# DIGITAL_OUTPUT.net
KiCad netlist of a schematic drawn in Altium Designer
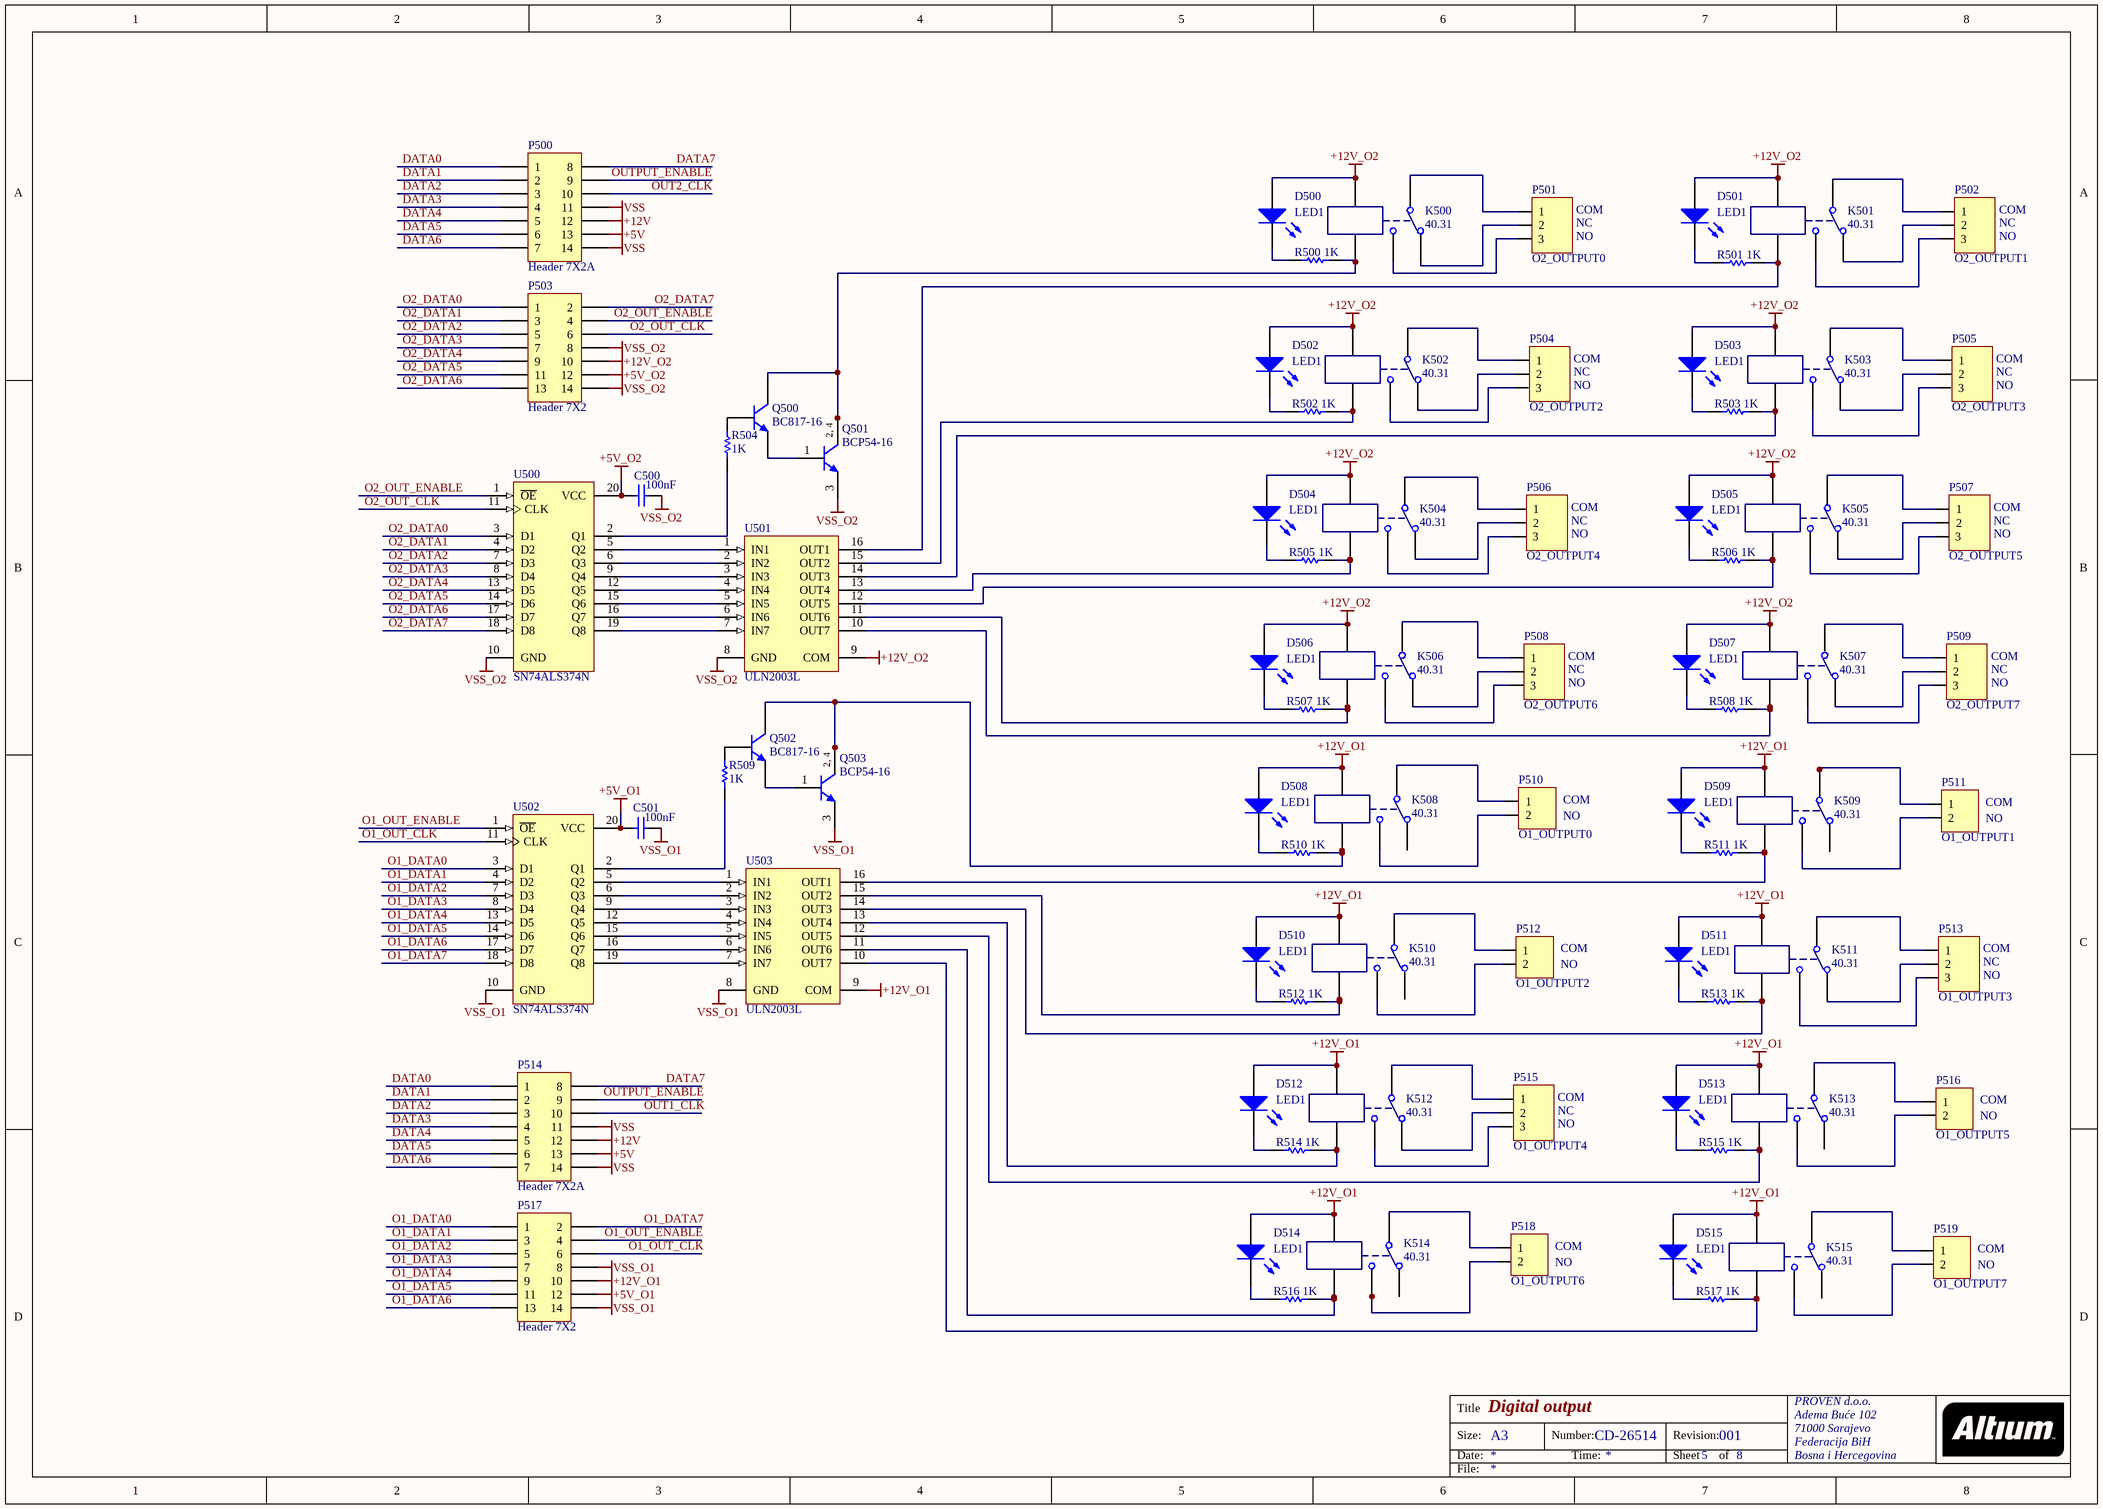
[diagram p0: DIGITAL_OUTPUT.SchDoc]

(export (version "E")
  (design (tool "Eeschema 10.0.6"))
  (components
    (comp (ref "C500")
      (value "100nF")
      (footprint "1206")
      (description "Ceramic Chip Capacitor - Standard")
      (fields (field (name "PUBLISHER") "Altium Limited"))
      (libsource (lib "KEMET Chip Capacitor") (part "C1206"))
    )
    (comp (ref "C501")
      (value "100nF")
      (footprint "1206")
      (description "Ceramic Chip Capacitor - Standard")
      (fields (field (name "PUBLISHER") "Altium Limited"))
      (libsource (lib "KEMET Chip Capacitor") (part "C1206"))
    )
    (comp (ref "D500")
      (value "LED1")
      (footprint "LED-1")
      (description "Typical RED GaAs LED")
      (fields (field (name "PUBLISHER") "Altium Limited"))
      (libsource (lib "Miscellaneous Devices") (part "LED1"))
    )
    (comp (ref "D501")
      (value "LED1")
      (footprint "LED-1")
      (description "Typical RED GaAs LED")
      (fields (field (name "PUBLISHER") "Altium Limited"))
      (libsource (lib "Miscellaneous Devices") (part "LED1"))
    )
    (comp (ref "D502")
      (value "LED1")
      (footprint "LED-1")
      (description "Typical RED GaAs LED")
      (fields (field (name "PUBLISHER") "Altium Limited"))
      (libsource (lib "Miscellaneous Devices") (part "LED1"))
    )
    (comp (ref "D503")
      (value "LED1")
      (footprint "LED-1")
      (description "Typical RED GaAs LED")
      (fields (field (name "PUBLISHER") "Altium Limited"))
      (libsource (lib "Miscellaneous Devices") (part "LED1"))
    )
    (comp (ref "D504")
      (value "LED1")
      (footprint "LED-1")
      (description "Typical RED GaAs LED")
      (fields (field (name "PUBLISHER") "Altium Limited"))
      (libsource (lib "Miscellaneous Devices") (part "LED1"))
    )
    (comp (ref "D505")
      (value "LED1")
      (footprint "LED-1")
      (description "Typical RED GaAs LED")
      (fields (field (name "PUBLISHER") "Altium Limited"))
      (libsource (lib "Miscellaneous Devices") (part "LED1"))
    )
    (comp (ref "D506")
      (value "LED1")
      (footprint "LED-1")
      (description "Typical RED GaAs LED")
      (fields (field (name "PUBLISHER") "Altium Limited"))
      (libsource (lib "Miscellaneous Devices") (part "LED1"))
    )
    (comp (ref "D507")
      (value "LED1")
      (footprint "LED-1")
      (description "Typical RED GaAs LED")
      (fields (field (name "PUBLISHER") "Altium Limited"))
      (libsource (lib "Miscellaneous Devices") (part "LED1"))
    )
    (comp (ref "D508")
      (value "LED1")
      (footprint "LED-1")
      (description "Typical RED GaAs LED")
      (fields (field (name "PUBLISHER") "Altium Limited"))
      (libsource (lib "Miscellaneous Devices") (part "LED1"))
    )
    (comp (ref "D509")
      (value "LED1")
      (footprint "LED-1")
      (description "Typical RED GaAs LED")
      (fields (field (name "PUBLISHER") "Altium Limited"))
      (libsource (lib "Miscellaneous Devices") (part "LED1"))
    )
    (comp (ref "D510")
      (value "LED1")
      (footprint "LED-1")
      (description "Typical RED GaAs LED")
      (fields (field (name "PUBLISHER") "Altium Limited"))
      (libsource (lib "Miscellaneous Devices") (part "LED1"))
    )
    (comp (ref "D511")
      (value "LED1")
      (footprint "LED-1")
      (description "Typical RED GaAs LED")
      (fields (field (name "PUBLISHER") "Altium Limited"))
      (libsource (lib "Miscellaneous Devices") (part "LED1"))
    )
    (comp (ref "D512")
      (value "LED1")
      (footprint "LED-1")
      (description "Typical RED GaAs LED")
      (fields (field (name "PUBLISHER") "Altium Limited"))
      (libsource (lib "Miscellaneous Devices") (part "LED1"))
    )
    (comp (ref "D513")
      (value "LED1")
      (footprint "LED-1")
      (description "Typical RED GaAs LED")
      (fields (field (name "PUBLISHER") "Altium Limited"))
      (libsource (lib "Miscellaneous Devices") (part "LED1"))
    )
    (comp (ref "D514")
      (value "LED1")
      (footprint "LED-1")
      (description "Typical RED GaAs LED")
      (fields (field (name "PUBLISHER") "Altium Limited"))
      (libsource (lib "Miscellaneous Devices") (part "LED1"))
    )
    (comp (ref "D515")
      (value "LED1")
      (footprint "LED-1")
      (description "Typical RED GaAs LED")
      (fields (field (name "PUBLISHER") "Altium Limited"))
      (libsource (lib "Miscellaneous Devices") (part "LED1"))
    )
    (comp (ref "K500")
      (value "40.31")
      (footprint "40.31 FINDER")
      (libsource (lib "") (part "FINDER 40.31_10"))
    )
    (comp (ref "K501")
      (value "40.31")
      (footprint "40.31 FINDER")
      (libsource (lib "") (part "FINDER 40.31_3"))
    )
    (comp (ref "K502")
      (value "40.31")
      (footprint "40.31 FINDER")
      (libsource (lib "") (part "FINDER 40.31_1"))
    )
    (comp (ref "K503")
      (value "40.31")
      (footprint "40.31 FINDER")
      (libsource (lib "") (part "FINDER 40.31_5"))
    )
    (comp (ref "K504")
      (value "40.31")
      (footprint "40.31 FINDER")
      (libsource (lib "") (part "FINDER 40.31_4"))
    )
    (comp (ref "K505")
      (value "40.31")
      (footprint "40.31 FINDER")
      (libsource (lib "") (part "FINDER 40.31_2"))
    )
    (comp (ref "K506")
      (value "40.31")
      (footprint "40.31 FINDER")
      (libsource (lib "") (part "FINDER 40.31_7"))
    )
    (comp (ref "K507")
      (value "40.31")
      (footprint "40.31 FINDER")
      (libsource (lib "") (part "FINDER 40.31_9"))
    )
    (comp (ref "K508")
      (value "40.31")
      (footprint "40.31 FINDER")
      (libsource (lib "FINDER 40.31") (part "FINDER 40.31"))
    )
    (comp (ref "K509")
      (value "40.31")
      (footprint "40.31 FINDER")
      (libsource (lib "") (part "FINDER 40.31_6"))
    )
    (comp (ref "K510")
      (value "40.31")
      (footprint "40.31 FINDER")
      (libsource (lib "FINDER 40.31") (part "FINDER 40.31"))
    )
    (comp (ref "K511")
      (value "40.31")
      (footprint "40.31 FINDER")
      (libsource (lib "") (part "FINDER 40.31_6"))
    )
    (comp (ref "K512")
      (value "40.31")
      (footprint "40.31 FINDER")
      (libsource (lib "FINDER 40.31") (part "FINDER 40.31"))
    )
    (comp (ref "K513")
      (value "40.31")
      (footprint "40.31 FINDER")
      (libsource (lib "") (part "FINDER 40.31_6"))
    )
    (comp (ref "K514")
      (value "40.31")
      (footprint "40.31 FINDER")
      (libsource (lib "") (part "FINDER 40.31_8"))
    )
    (comp (ref "K515")
      (value "40.31")
      (footprint "40.31 FINDER")
      (libsource (lib "") (part "FINDER 40.31_6"))
    )
    (comp (ref "P500")
      (value "Header 7X2A")
      (footprint "HDR2X7_CEN")
      (description "Header, 7-Pin, Dual row")
      (fields (field (name "PUBLISHER") "Altium Limited"))
      (libsource (lib "Miscellaneous Connectors") (part "Header 7X2A"))
    )
    (comp (ref "P501")
      (value "O2_OUTPUT0")
      (footprint "TERMINAL BLOK")
      (description "Terminal blok")
      (libsource (lib "") (part "Terminal blok 3 pina_1"))
    )
    (comp (ref "P502")
      (value "O2_OUTPUT1")
      (footprint "TERMINAL BLOK")
      (description "Terminal blok")
      (libsource (lib "") (part "Terminal blok 3 pina_3"))
    )
    (comp (ref "P503")
      (value "Header 7X2")
      (footprint "HDR2X7")
      (description "Header, 7-Pin, Dual row")
      (fields (field (name "PUBLISHER") "Altium Limited"))
      (libsource (lib "Miscellaneous Connectors") (part "Header 7X2"))
    )
    (comp (ref "P504")
      (value "O2_OUTPUT2")
      (footprint "TERMINAL BLOK")
      (description "Terminal blok")
      (libsource (lib "") (part "Terminal blok 3 pina_2"))
    )
    (comp (ref "P505")
      (value "O2_OUTPUT3")
      (footprint "TERMINAL BLOK")
      (description "Terminal blok")
      (libsource (lib "TERMINAL_CONNECOR_3") (part "Terminal blok 3 pina"))
    )
    (comp (ref "P506")
      (value "O2_OUTPUT4")
      (footprint "TERMINAL BLOK")
      (description "Terminal blok")
      (libsource (lib "") (part "Terminal blok 3 pina_2"))
    )
    (comp (ref "P507")
      (value "O2_OUTPUT5")
      (footprint "TERMINAL BLOK")
      (description "Terminal blok")
      (libsource (lib "TERMINAL_CONNECOR_3") (part "Terminal blok 3 pina"))
    )
    (comp (ref "P508")
      (value "O2_OUTPUT6")
      (footprint "TERMINAL BLOK")
      (description "Terminal blok")
      (libsource (lib "") (part "Terminal blok 3 pina_2"))
    )
    (comp (ref "P509")
      (value "O2_OUTPUT7")
      (footprint "TERMINAL BLOK")
      (description "Terminal blok")
      (libsource (lib "TERMINAL_CONNECOR_3") (part "Terminal blok 3 pina"))
    )
    (comp (ref "P510")
      (value "O1_OUTPUT0")
      (footprint "TERMINAL BLOK 2")
      (description "Terminal blok 2")
      (libsource (lib "") (part "Terminal blok 2 pina_1"))
    )
    (comp (ref "P511")
      (value "O1_OUTPUT1")
      (footprint "TERMINAL BLOK 2")
      (description "Terminal blok 2")
      (libsource (lib "") (part "Terminal blok 2 pina_3"))
    )
    (comp (ref "P512")
      (value "O1_OUTPUT2")
      (footprint "TERMINAL BLOK 2")
      (description "Terminal blok 2")
      (libsource (lib "") (part "Terminal blok 2 pina_1"))
    )
    (comp (ref "P513")
      (value "O1_OUTPUT3")
      (footprint "TERMINAL BLOK")
      (description "Terminal blok")
      (libsource (lib "TERMINAL_CONNECOR_3") (part "Terminal blok 3 pina"))
    )
    (comp (ref "P514")
      (value "Header 7X2A")
      (footprint "HDR2X7_CEN")
      (description "Header, 7-Pin, Dual row")
      (fields (field (name "PUBLISHER") "Altium Limited"))
      (libsource (lib "Miscellaneous Connectors") (part "Header 7X2A"))
    )
    (comp (ref "P515")
      (value "O1_OUTPUT4")
      (footprint "TERMINAL BLOK")
      (description "Terminal blok")
      (libsource (lib "") (part "Terminal blok 3 pina_2"))
    )
    (comp (ref "P516")
      (value "O1_OUTPUT5")
      (footprint "TERMINAL BLOK 2")
      (description "Terminal blok 2")
      (libsource (lib "") (part "Terminal blok 2 pina_3"))
    )
    (comp (ref "P517")
      (value "Header 7X2")
      (footprint "HDR2X7")
      (description "Header, 7-Pin, Dual row")
      (fields (field (name "PUBLISHER") "Altium Limited"))
      (libsource (lib "Miscellaneous Connectors") (part "Header 7X2"))
    )
    (comp (ref "P518")
      (value "O1_OUTPUT6")
      (footprint "TERMINAL BLOK 2")
      (description "Terminal blok 2")
      (libsource (lib "") (part "Terminal blok 2 pina_2"))
    )
    (comp (ref "P519")
      (value "O1_OUTPUT7")
      (footprint "TERMINAL BLOK 2")
      (description "Terminal blok 2")
      (libsource (lib "TERMINAL_CONNECOR_2") (part "Terminal blok 2 pina"))
    )
    (comp (ref "Q500")
      (value "BC817-16")
      (footprint "SOT23_N")
      (description "NPN General-purpose Transistor")
      (fields (field (name "PUBLISHER") "Altium Limited"))
      (libsource (lib "Philips Discrete BJT - Low Power") (part "BC817-16"))
    )
    (comp (ref "Q501")
      (value "BCP54-16")
      (footprint "SOT223_N")
      (description "NPN Medium Power Transistor")
      (fields (field (name "PUBLISHER") "Altium Limited"))
      (libsource (lib "Philips Discrete BJT - Medium Power") (part "BCP54-16"))
    )
    (comp (ref "Q502")
      (value "BC817-16")
      (footprint "SOT23_N")
      (description "NPN General-purpose Transistor")
      (fields (field (name "PUBLISHER") "Altium Limited"))
      (libsource (lib "Philips Discrete BJT - Low Power") (part "BC817-16"))
    )
    (comp (ref "Q503")
      (value "BCP54-16")
      (footprint "SOT223_N")
      (description "NPN Medium Power Transistor")
      (fields (field (name "PUBLISHER") "Altium Limited"))
      (libsource (lib "Philips Discrete BJT - Medium Power") (part "BCP54-16"))
    )
    (comp (ref "R500")
      (value "1K")
      (footprint "ERA-0805")
      (fields (field (name "PUBLISHER") "Altium Limited"))
      (libsource (lib "Panasonic Resistor") (part "ERAS"))
    )
    (comp (ref "R501")
      (value "1K")
      (footprint "ERA-0805")
      (fields (field (name "PUBLISHER") "Altium Limited"))
      (libsource (lib "Panasonic Resistor") (part "ERAS"))
    )
    (comp (ref "R502")
      (value "1K")
      (footprint "ERA-0805")
      (fields (field (name "PUBLISHER") "Altium Limited"))
      (libsource (lib "Panasonic Resistor") (part "ERAS"))
    )
    (comp (ref "R503")
      (value "1K")
      (footprint "ERA-0805")
      (fields (field (name "PUBLISHER") "Altium Limited"))
      (libsource (lib "Panasonic Resistor") (part "ERAS"))
    )
    (comp (ref "R504")
      (value "1K")
      (footprint "ERA-0805")
      (fields (field (name "PUBLISHER") "Altium Limited"))
      (libsource (lib "Panasonic Resistor") (part "ERAS"))
    )
    (comp (ref "R505")
      (value "1K")
      (footprint "ERA-0805")
      (fields (field (name "PUBLISHER") "Altium Limited"))
      (libsource (lib "Panasonic Resistor") (part "ERAS"))
    )
    (comp (ref "R506")
      (value "1K")
      (footprint "ERA-0805")
      (fields (field (name "PUBLISHER") "Altium Limited"))
      (libsource (lib "Panasonic Resistor") (part "ERAS"))
    )
    (comp (ref "R507")
      (value "1K")
      (footprint "ERA-0805")
      (fields (field (name "PUBLISHER") "Altium Limited"))
      (libsource (lib "Panasonic Resistor") (part "ERAS"))
    )
    (comp (ref "R508")
      (value "1K")
      (footprint "ERA-0805")
      (fields (field (name "PUBLISHER") "Altium Limited"))
      (libsource (lib "Panasonic Resistor") (part "ERAS"))
    )
    (comp (ref "R509")
      (value "1K")
      (footprint "ERA-0805")
      (fields (field (name "PUBLISHER") "Altium Limited"))
      (libsource (lib "Panasonic Resistor") (part "ERAS"))
    )
    (comp (ref "R510")
      (value "1K")
      (footprint "ERA-0805")
      (fields (field (name "PUBLISHER") "Altium Limited"))
      (libsource (lib "Panasonic Resistor") (part "ERAS"))
    )
    (comp (ref "R511")
      (value "1K")
      (footprint "ERA-0805")
      (fields (field (name "PUBLISHER") "Altium Limited"))
      (libsource (lib "Panasonic Resistor") (part "ERAS"))
    )
    (comp (ref "R512")
      (value "1K")
      (footprint "ERA-0805")
      (fields (field (name "PUBLISHER") "Altium Limited"))
      (libsource (lib "Panasonic Resistor") (part "ERAS"))
    )
    (comp (ref "R513")
      (value "1K")
      (footprint "ERA-0805")
      (fields (field (name "PUBLISHER") "Altium Limited"))
      (libsource (lib "Panasonic Resistor") (part "ERAS"))
    )
    (comp (ref "R514")
      (value "1K")
      (footprint "ERA-0805")
      (fields (field (name "PUBLISHER") "Altium Limited"))
      (libsource (lib "Panasonic Resistor") (part "ERAS"))
    )
    (comp (ref "R515")
      (value "1K")
      (footprint "ERA-0805")
      (fields (field (name "PUBLISHER") "Altium Limited"))
      (libsource (lib "Panasonic Resistor") (part "ERAS"))
    )
    (comp (ref "R516")
      (value "1K")
      (footprint "ERA-0805")
      (fields (field (name "PUBLISHER") "Altium Limited"))
      (libsource (lib "Panasonic Resistor") (part "ERAS"))
    )
    (comp (ref "R517")
      (value "1K")
      (footprint "ERA-0805")
      (fields (field (name "PUBLISHER") "Altium Limited"))
      (libsource (lib "Panasonic Resistor") (part "ERAS"))
    )
    (comp (ref "U500")
      (value "SN74ALS374N")
      (footprint "N020D")
      (description "Octal D-Type Edge-Triggered Flip-Flop with 3-State Outputs")
      (fields (field (name "PUBLISHER") "Altium Limited"))
      (libsource (lib "TI Logic Flip-Flop") (part "SN74ALS374N"))
    )
    (comp (ref "U501")
      (value "ULN2003L")
      (footprint "L16_N")
      (description "High-Voltage, High-Current Darlington Array")
      (fields (field (name "PUBLISHER") "Altium Limited"))
      (libsource (lib "Allegro Interface Darlington Driver") (part "ULN2003L"))
    )
    (comp (ref "U502")
      (value "SN74ALS374N")
      (footprint "N020D")
      (description "Octal D-Type Edge-Triggered Flip-Flop with 3-State Outputs")
      (fields (field (name "PUBLISHER") "Altium Limited"))
      (libsource (lib "TI Logic Flip-Flop") (part "SN74ALS374N"))
    )
    (comp (ref "U503")
      (value "ULN2003L")
      (footprint "L16_N")
      (description "High-Voltage, High-Current Darlington Array")
      (fields (field (name "PUBLISHER") "Altium Limited"))
      (libsource (lib "Allegro Interface Darlington Driver") (part "ULN2003L"))
    )
  )
  (nets
    (net (code "1") (name "+5V") (class "Default")
      (node (ref "P500") (pin "13") (pinfunction "13_13") (pintype "passive"))
      (node (ref "P514") (pin "13") (pinfunction "13_13") (pintype "passive"))
    )
    (net (code "2") (name "+5V_O1") (class "Default")
      (node (ref "C501") (pin "1") (pinfunction "1_1") (pintype "passive"))
      (node (ref "P517") (pin "12") (pinfunction "12_12") (pintype "passive"))
      (node (ref "U502") (pin "20") (pinfunction "VCC_20") (pintype "power_in"))
    )
    (net (code "3") (name "+5V_O2") (class "Default")
      (node (ref "C500") (pin "1") (pinfunction "1_1") (pintype "passive"))
      (node (ref "P503") (pin "12") (pinfunction "12_12") (pintype "passive"))
      (node (ref "U500") (pin "20") (pinfunction "VCC_20") (pintype "power_in"))
    )
    (net (code "4") (name "+12V") (class "Default")
      (node (ref "P500") (pin "12") (pinfunction "12_12") (pintype "passive"))
      (node (ref "P514") (pin "12") (pinfunction "12_12") (pintype "passive"))
    )
    (net (code "5") (name "+12V_O1") (class "Default")
      (node (ref "D508") (pin "1") (pinfunction "A_1") (pintype "passive"))
      (node (ref "D509") (pin "1") (pinfunction "A_1") (pintype "passive"))
      (node (ref "D510") (pin "1") (pinfunction "A_1") (pintype "passive"))
      (node (ref "D511") (pin "1") (pinfunction "A_1") (pintype "passive"))
      (node (ref "D512") (pin "1") (pinfunction "A_1") (pintype "passive"))
      (node (ref "D513") (pin "1") (pinfunction "A_1") (pintype "passive"))
      (node (ref "D514") (pin "1") (pinfunction "A_1") (pintype "passive"))
      (node (ref "D515") (pin "1") (pinfunction "A_1") (pintype "passive"))
      (node (ref "K508") (pin "1") (pinfunction "1_1") (pintype "passive"))
      (node (ref "K509") (pin "1") (pinfunction "1_1") (pintype "passive"))
      (node (ref "K510") (pin "1") (pinfunction "1_1") (pintype "passive"))
      (node (ref "K511") (pin "1") (pinfunction "1_1") (pintype "passive"))
      (node (ref "K512") (pin "1") (pinfunction "1_1") (pintype "passive"))
      (node (ref "K513") (pin "1") (pinfunction "1_1") (pintype "passive"))
      (node (ref "K514") (pin "1") (pinfunction "1_1") (pintype "passive"))
      (node (ref "K515") (pin "1") (pinfunction "1_1") (pintype "passive"))
      (node (ref "P517") (pin "10") (pinfunction "10_10") (pintype "passive"))
      (node (ref "U503") (pin "9") (pinfunction "COM_9") (pintype "passive"))
    )
    (net (code "6") (name "+12V_O2") (class "Default")
      (node (ref "D500") (pin "1") (pinfunction "A_1") (pintype "passive"))
      (node (ref "D501") (pin "1") (pinfunction "A_1") (pintype "passive"))
      (node (ref "D502") (pin "1") (pinfunction "A_1") (pintype "passive"))
      (node (ref "D503") (pin "1") (pinfunction "A_1") (pintype "passive"))
      (node (ref "D504") (pin "1") (pinfunction "A_1") (pintype "passive"))
      (node (ref "D505") (pin "1") (pinfunction "A_1") (pintype "passive"))
      (node (ref "D506") (pin "1") (pinfunction "A_1") (pintype "passive"))
      (node (ref "D507") (pin "1") (pinfunction "A_1") (pintype "passive"))
      (node (ref "K500") (pin "1") (pinfunction "1_1") (pintype "passive"))
      (node (ref "K501") (pin "1") (pinfunction "1_1") (pintype "passive"))
      (node (ref "K502") (pin "1") (pinfunction "1_1") (pintype "passive"))
      (node (ref "K503") (pin "1") (pinfunction "1_1") (pintype "passive"))
      (node (ref "K504") (pin "1") (pinfunction "1_1") (pintype "passive"))
      (node (ref "K505") (pin "1") (pinfunction "1_1") (pintype "passive"))
      (node (ref "K506") (pin "1") (pinfunction "1_1") (pintype "passive"))
      (node (ref "K507") (pin "1") (pinfunction "1_1") (pintype "passive"))
      (node (ref "P503") (pin "10") (pinfunction "10_10") (pintype "passive"))
      (node (ref "U501") (pin "9") (pinfunction "COM_9") (pintype "passive"))
    )
    (net (code "7") (name "/DATA0") (class "Default")
      (node (ref "P500") (pin "1") (pinfunction "1_1") (pintype "passive"))
      (node (ref "P514") (pin "1") (pinfunction "1_1") (pintype "passive"))
    )
    (net (code "8") (name "/DATA1") (class "Default")
      (node (ref "P500") (pin "2") (pinfunction "2_2") (pintype "passive"))
      (node (ref "P514") (pin "2") (pinfunction "2_2") (pintype "passive"))
    )
    (net (code "9") (name "/DATA2") (class "Default")
      (node (ref "P500") (pin "3") (pinfunction "3_3") (pintype "passive"))
      (node (ref "P514") (pin "3") (pinfunction "3_3") (pintype "passive"))
    )
    (net (code "10") (name "/DATA3") (class "Default")
      (node (ref "P500") (pin "4") (pinfunction "4_4") (pintype "passive"))
      (node (ref "P514") (pin "4") (pinfunction "4_4") (pintype "passive"))
    )
    (net (code "11") (name "/DATA4") (class "Default")
      (node (ref "P500") (pin "5") (pinfunction "5_5") (pintype "passive"))
      (node (ref "P514") (pin "5") (pinfunction "5_5") (pintype "passive"))
    )
    (net (code "12") (name "/DATA5") (class "Default")
      (node (ref "P500") (pin "6") (pinfunction "6_6") (pintype "passive"))
      (node (ref "P514") (pin "6") (pinfunction "6_6") (pintype "passive"))
    )
    (net (code "13") (name "/DATA6") (class "Default")
      (node (ref "P500") (pin "7") (pinfunction "7_7") (pintype "passive"))
      (node (ref "P514") (pin "7") (pinfunction "7_7") (pintype "passive"))
    )
    (net (code "14") (name "/DATA7") (class "Default")
      (node (ref "P500") (pin "8") (pinfunction "8_8") (pintype "passive"))
      (node (ref "P514") (pin "8") (pinfunction "8_8") (pintype "passive"))
    )
    (net (code "15") (name "/O1_DATA0") (class "Default")
      (node (ref "P517") (pin "1") (pinfunction "1_1") (pintype "passive"))
      (node (ref "U502") (pin "3") (pinfunction "D1_3") (pintype "input"))
    )
    (net (code "16") (name "/O1_DATA1") (class "Default")
      (node (ref "P517") (pin "3") (pinfunction "3_3") (pintype "passive"))
      (node (ref "U502") (pin "4") (pinfunction "D2_4") (pintype "input"))
    )
    (net (code "17") (name "/O1_DATA2") (class "Default")
      (node (ref "P517") (pin "5") (pinfunction "5_5") (pintype "passive"))
      (node (ref "U502") (pin "7") (pinfunction "D3_7") (pintype "input"))
    )
    (net (code "18") (name "/O1_DATA3") (class "Default")
      (node (ref "P517") (pin "7") (pinfunction "7_7") (pintype "passive"))
      (node (ref "U502") (pin "8") (pinfunction "D4_8") (pintype "input"))
    )
    (net (code "19") (name "/O1_DATA4") (class "Default")
      (node (ref "P517") (pin "9") (pinfunction "9_9") (pintype "passive"))
      (node (ref "U502") (pin "13") (pinfunction "D5_13") (pintype "input"))
    )
    (net (code "20") (name "/O1_DATA5") (class "Default")
      (node (ref "P517") (pin "11") (pinfunction "11_11") (pintype "passive"))
      (node (ref "U502") (pin "14") (pinfunction "D6_14") (pintype "input"))
    )
    (net (code "21") (name "/O1_DATA6") (class "Default")
      (node (ref "P517") (pin "13") (pinfunction "13_13") (pintype "passive"))
      (node (ref "U502") (pin "17") (pinfunction "D7_17") (pintype "input"))
    )
    (net (code "22") (name "/O1_DATA7") (class "Default")
      (node (ref "P517") (pin "2") (pinfunction "2_2") (pintype "passive"))
      (node (ref "U502") (pin "18") (pinfunction "D8_18") (pintype "input"))
    )
    (net (code "23") (name "/O1_OUT_CLK") (class "Default")
      (node (ref "P517") (pin "6") (pinfunction "6_6") (pintype "passive"))
      (node (ref "U502") (pin "11") (pinfunction "CLK_11") (pintype "input"))
    )
    (net (code "24") (name "/O1_OUT_ENABLE") (class "Default")
      (node (ref "P517") (pin "4") (pinfunction "4_4") (pintype "passive"))
      (node (ref "U502") (pin "1") (pinfunction "~{OE}_1") (pintype "input"))
    )
    (net (code "25") (name "/O2_DATA0") (class "Default")
      (node (ref "P503") (pin "1") (pinfunction "1_1") (pintype "passive"))
      (node (ref "U500") (pin "3") (pinfunction "D1_3") (pintype "input"))
    )
    (net (code "26") (name "/O2_DATA1") (class "Default")
      (node (ref "P503") (pin "3") (pinfunction "3_3") (pintype "passive"))
      (node (ref "U500") (pin "4") (pinfunction "D2_4") (pintype "input"))
    )
    (net (code "27") (name "/O2_DATA2") (class "Default")
      (node (ref "P503") (pin "5") (pinfunction "5_5") (pintype "passive"))
      (node (ref "U500") (pin "7") (pinfunction "D3_7") (pintype "input"))
    )
    (net (code "28") (name "/O2_DATA3") (class "Default")
      (node (ref "P503") (pin "7") (pinfunction "7_7") (pintype "passive"))
      (node (ref "U500") (pin "8") (pinfunction "D4_8") (pintype "input"))
    )
    (net (code "29") (name "/O2_DATA4") (class "Default")
      (node (ref "P503") (pin "9") (pinfunction "9_9") (pintype "passive"))
      (node (ref "U500") (pin "13") (pinfunction "D5_13") (pintype "input"))
    )
    (net (code "30") (name "/O2_DATA5") (class "Default")
      (node (ref "P503") (pin "11") (pinfunction "11_11") (pintype "passive"))
      (node (ref "U500") (pin "14") (pinfunction "D6_14") (pintype "input"))
    )
    (net (code "31") (name "/O2_DATA6") (class "Default")
      (node (ref "P503") (pin "13") (pinfunction "13_13") (pintype "passive"))
      (node (ref "U500") (pin "17") (pinfunction "D7_17") (pintype "input"))
    )
    (net (code "32") (name "/O2_DATA7") (class "Default")
      (node (ref "P503") (pin "2") (pinfunction "2_2") (pintype "passive"))
      (node (ref "U500") (pin "18") (pinfunction "D8_18") (pintype "input"))
    )
    (net (code "33") (name "/O2_OUT_CLK") (class "Default")
      (node (ref "P503") (pin "6") (pinfunction "6_6") (pintype "passive"))
      (node (ref "U500") (pin "11") (pinfunction "CLK_11") (pintype "input"))
    )
    (net (code "34") (name "/O2_OUT_ENABLE") (class "Default")
      (node (ref "P503") (pin "4") (pinfunction "4_4") (pintype "passive"))
      (node (ref "U500") (pin "1") (pinfunction "~{OE}_1") (pintype "input"))
    )
    (net (code "35") (name "/OUT1_CLK") (class "Default")
      (node (ref "P514") (pin "10") (pinfunction "10_10") (pintype "passive"))
    )
    (net (code "36") (name "/OUT2_CLK") (class "Default")
      (node (ref "P500") (pin "10") (pinfunction "10_10") (pintype "passive"))
    )
    (net (code "37") (name "/OUTPUT_ENABLE") (class "Default")
      (node (ref "P500") (pin "9") (pinfunction "9_9") (pintype "passive"))
      (node (ref "P514") (pin "9") (pinfunction "9_9") (pintype "passive"))
    )
    (net (code "38") (name "Net-(D500-K)") (class "Default")
      (node (ref "D500") (pin "2") (pinfunction "K_2") (pintype "passive"))
      (node (ref "R500") (pin "1") (pinfunction "1_1") (pintype "passive"))
    )
    (net (code "39") (name "Net-(D501-K)") (class "Default")
      (node (ref "D501") (pin "2") (pinfunction "K_2") (pintype "passive"))
      (node (ref "R501") (pin "1") (pinfunction "1_1") (pintype "passive"))
    )
    (net (code "40") (name "Net-(D502-K)") (class "Default")
      (node (ref "D502") (pin "2") (pinfunction "K_2") (pintype "passive"))
      (node (ref "R502") (pin "1") (pinfunction "1_1") (pintype "passive"))
    )
    (net (code "41") (name "Net-(D503-K)") (class "Default")
      (node (ref "D503") (pin "2") (pinfunction "K_2") (pintype "passive"))
      (node (ref "R503") (pin "1") (pinfunction "1_1") (pintype "passive"))
    )
    (net (code "42") (name "Net-(D504-K)") (class "Default")
      (node (ref "D504") (pin "2") (pinfunction "K_2") (pintype "passive"))
      (node (ref "R505") (pin "1") (pinfunction "1_1") (pintype "passive"))
    )
    (net (code "43") (name "Net-(D505-K)") (class "Default")
      (node (ref "D505") (pin "2") (pinfunction "K_2") (pintype "passive"))
      (node (ref "R506") (pin "1") (pinfunction "1_1") (pintype "passive"))
    )
    (net (code "44") (name "Net-(D506-K)") (class "Default")
      (node (ref "D506") (pin "2") (pinfunction "K_2") (pintype "passive"))
      (node (ref "R507") (pin "1") (pinfunction "1_1") (pintype "passive"))
    )
    (net (code "45") (name "Net-(D507-K)") (class "Default")
      (node (ref "D507") (pin "2") (pinfunction "K_2") (pintype "passive"))
      (node (ref "R508") (pin "1") (pinfunction "1_1") (pintype "passive"))
    )
    (net (code "46") (name "Net-(D508-K)") (class "Default")
      (node (ref "D508") (pin "2") (pinfunction "K_2") (pintype "passive"))
      (node (ref "R510") (pin "1") (pinfunction "1_1") (pintype "passive"))
    )
    (net (code "47") (name "Net-(D509-K)") (class "Default")
      (node (ref "D509") (pin "2") (pinfunction "K_2") (pintype "passive"))
      (node (ref "R511") (pin "1") (pinfunction "1_1") (pintype "passive"))
    )
    (net (code "48") (name "Net-(D510-K)") (class "Default")
      (node (ref "D510") (pin "2") (pinfunction "K_2") (pintype "passive"))
      (node (ref "R512") (pin "1") (pinfunction "1_1") (pintype "passive"))
    )
    (net (code "49") (name "Net-(D511-K)") (class "Default")
      (node (ref "D511") (pin "2") (pinfunction "K_2") (pintype "passive"))
      (node (ref "R513") (pin "1") (pinfunction "1_1") (pintype "passive"))
    )
    (net (code "50") (name "Net-(D512-K)") (class "Default")
      (node (ref "D512") (pin "2") (pinfunction "K_2") (pintype "passive"))
      (node (ref "R514") (pin "1") (pinfunction "1_1") (pintype "passive"))
    )
    (net (code "51") (name "Net-(D513-K)") (class "Default")
      (node (ref "D513") (pin "2") (pinfunction "K_2") (pintype "passive"))
      (node (ref "R515") (pin "1") (pinfunction "1_1") (pintype "passive"))
    )
    (net (code "52") (name "Net-(D514-K)") (class "Default")
      (node (ref "D514") (pin "2") (pinfunction "K_2") (pintype "passive"))
      (node (ref "R516") (pin "1") (pinfunction "1_1") (pintype "passive"))
    )
    (net (code "53") (name "Net-(D515-K)") (class "Default")
      (node (ref "D515") (pin "2") (pinfunction "K_2") (pintype "passive"))
      (node (ref "R517") (pin "1") (pinfunction "1_1") (pintype "passive"))
    )
    (net (code "54") (name "Net-(K500-Pad3)") (class "Default")
      (node (ref "K500") (pin "3") (pinfunction "3_3") (pintype "passive"))
      (node (ref "P501") (pin "1") (pinfunction "1_1") (pintype "passive"))
    )
    (net (code "55") (name "Net-(K500-Pad4)") (class "Default")
      (node (ref "K500") (pin "4") (pinfunction "4_4") (pintype "passive"))
      (node (ref "P501") (pin "3") (pinfunction "3_3") (pintype "passive"))
    )
    (net (code "56") (name "Net-(K500-Pad5)") (class "Default")
      (node (ref "K500") (pin "5") (pinfunction "5_5") (pintype "passive"))
      (node (ref "P501") (pin "2") (pinfunction "2_2") (pintype "passive"))
    )
    (net (code "57") (name "Net-(K501-Pad3)") (class "Default")
      (node (ref "K501") (pin "3") (pinfunction "3_3") (pintype "passive"))
      (node (ref "P502") (pin "1") (pinfunction "1_1") (pintype "passive"))
    )
    (net (code "58") (name "Net-(K501-Pad4)") (class "Default")
      (node (ref "K501") (pin "4") (pinfunction "4_4") (pintype "passive"))
      (node (ref "P502") (pin "3") (pinfunction "3_3") (pintype "passive"))
    )
    (net (code "59") (name "Net-(K501-Pad5)") (class "Default")
      (node (ref "K501") (pin "5") (pinfunction "5_5") (pintype "passive"))
      (node (ref "P502") (pin "2") (pinfunction "2_2") (pintype "passive"))
    )
    (net (code "60") (name "Net-(K502-Pad3)") (class "Default")
      (node (ref "K502") (pin "3") (pinfunction "3_3") (pintype "passive"))
      (node (ref "P504") (pin "1") (pinfunction "1_1") (pintype "passive"))
    )
    (net (code "61") (name "Net-(K502-Pad4)") (class "Default")
      (node (ref "K502") (pin "4") (pinfunction "4_4") (pintype "passive"))
      (node (ref "P504") (pin "3") (pinfunction "3_3") (pintype "passive"))
    )
    (net (code "62") (name "Net-(K502-Pad5)") (class "Default")
      (node (ref "K502") (pin "5") (pinfunction "5_5") (pintype "passive"))
      (node (ref "P504") (pin "2") (pinfunction "2_2") (pintype "passive"))
    )
    (net (code "63") (name "Net-(K503-Pad3)") (class "Default")
      (node (ref "K503") (pin "3") (pinfunction "3_3") (pintype "passive"))
      (node (ref "P505") (pin "1") (pinfunction "1_1") (pintype "passive"))
    )
    (net (code "64") (name "Net-(K503-Pad4)") (class "Default")
      (node (ref "K503") (pin "4") (pinfunction "4_4") (pintype "passive"))
      (node (ref "P505") (pin "3") (pinfunction "3_3") (pintype "passive"))
    )
    (net (code "65") (name "Net-(K503-Pad5)") (class "Default")
      (node (ref "K503") (pin "5") (pinfunction "5_5") (pintype "passive"))
      (node (ref "P505") (pin "2") (pinfunction "2_2") (pintype "passive"))
    )
    (net (code "66") (name "Net-(K504-Pad3)") (class "Default")
      (node (ref "K504") (pin "3") (pinfunction "3_3") (pintype "passive"))
      (node (ref "P506") (pin "1") (pinfunction "1_1") (pintype "passive"))
    )
    (net (code "67") (name "Net-(K504-Pad4)") (class "Default")
      (node (ref "K504") (pin "4") (pinfunction "4_4") (pintype "passive"))
      (node (ref "P506") (pin "3") (pinfunction "3_3") (pintype "passive"))
    )
    (net (code "68") (name "Net-(K504-Pad5)") (class "Default")
      (node (ref "K504") (pin "5") (pinfunction "5_5") (pintype "passive"))
      (node (ref "P506") (pin "2") (pinfunction "2_2") (pintype "passive"))
    )
    (net (code "69") (name "Net-(K505-Pad3)") (class "Default")
      (node (ref "K505") (pin "3") (pinfunction "3_3") (pintype "passive"))
      (node (ref "P507") (pin "1") (pinfunction "1_1") (pintype "passive"))
    )
    (net (code "70") (name "Net-(K505-Pad4)") (class "Default")
      (node (ref "K505") (pin "4") (pinfunction "4_4") (pintype "passive"))
      (node (ref "P507") (pin "3") (pinfunction "3_3") (pintype "passive"))
    )
    (net (code "71") (name "Net-(K505-Pad5)") (class "Default")
      (node (ref "K505") (pin "5") (pinfunction "5_5") (pintype "passive"))
      (node (ref "P507") (pin "2") (pinfunction "2_2") (pintype "passive"))
    )
    (net (code "72") (name "Net-(K506-Pad3)") (class "Default")
      (node (ref "K506") (pin "3") (pinfunction "3_3") (pintype "passive"))
      (node (ref "P508") (pin "1") (pinfunction "1_1") (pintype "passive"))
    )
    (net (code "73") (name "Net-(K506-Pad4)") (class "Default")
      (node (ref "K506") (pin "4") (pinfunction "4_4") (pintype "passive"))
      (node (ref "P508") (pin "3") (pinfunction "3_3") (pintype "passive"))
    )
    (net (code "74") (name "Net-(K506-Pad5)") (class "Default")
      (node (ref "K506") (pin "5") (pinfunction "5_5") (pintype "passive"))
      (node (ref "P508") (pin "2") (pinfunction "2_2") (pintype "passive"))
    )
    (net (code "75") (name "Net-(K507-Pad3)") (class "Default")
      (node (ref "K507") (pin "3") (pinfunction "3_3") (pintype "passive"))
      (node (ref "P509") (pin "1") (pinfunction "1_1") (pintype "passive"))
    )
    (net (code "76") (name "Net-(K507-Pad4)") (class "Default")
      (node (ref "K507") (pin "4") (pinfunction "4_4") (pintype "passive"))
      (node (ref "P509") (pin "3") (pinfunction "3_3") (pintype "passive"))
    )
    (net (code "77") (name "Net-(K507-Pad5)") (class "Default")
      (node (ref "K507") (pin "5") (pinfunction "5_5") (pintype "passive"))
      (node (ref "P509") (pin "2") (pinfunction "2_2") (pintype "passive"))
    )
    (net (code "78") (name "Net-(K508-Pad3)") (class "Default")
      (node (ref "K508") (pin "3") (pinfunction "3_3") (pintype "passive"))
      (node (ref "P510") (pin "1") (pinfunction "1_1") (pintype "passive"))
    )
    (net (code "79") (name "Net-(K508-Pad4)") (class "Default")
      (node (ref "K508") (pin "4") (pinfunction "4_4") (pintype "passive"))
      (node (ref "P510") (pin "2") (pinfunction "2_2") (pintype "passive"))
    )
    (net (code "80") (name "Net-(K509-Pad3)") (class "Default")
      (node (ref "K509") (pin "3") (pinfunction "3_3") (pintype "passive"))
      (node (ref "P511") (pin "1") (pinfunction "1_1") (pintype "passive"))
    )
    (net (code "81") (name "Net-(K509-Pad4)") (class "Default")
      (node (ref "K509") (pin "4") (pinfunction "4_4") (pintype "passive"))
      (node (ref "P511") (pin "2") (pinfunction "2_2") (pintype "passive"))
    )
    (net (code "82") (name "Net-(K510-Pad3)") (class "Default")
      (node (ref "K510") (pin "3") (pinfunction "3_3") (pintype "passive"))
      (node (ref "P512") (pin "1") (pinfunction "1_1") (pintype "passive"))
    )
    (net (code "83") (name "Net-(K510-Pad4)") (class "Default")
      (node (ref "K510") (pin "4") (pinfunction "4_4") (pintype "passive"))
      (node (ref "P512") (pin "2") (pinfunction "2_2") (pintype "passive"))
    )
    (net (code "84") (name "Net-(K511-Pad3)") (class "Default")
      (node (ref "K511") (pin "3") (pinfunction "3_3") (pintype "passive"))
      (node (ref "P513") (pin "1") (pinfunction "1_1") (pintype "passive"))
    )
    (net (code "85") (name "Net-(K511-Pad4)") (class "Default")
      (node (ref "K511") (pin "4") (pinfunction "4_4") (pintype "passive"))
      (node (ref "P513") (pin "3") (pinfunction "3_3") (pintype "passive"))
    )
    (net (code "86") (name "Net-(K511-Pad5)") (class "Default")
      (node (ref "K511") (pin "5") (pinfunction "5_5") (pintype "passive"))
      (node (ref "P513") (pin "2") (pinfunction "2_2") (pintype "passive"))
    )
    (net (code "87") (name "Net-(K512-Pad3)") (class "Default")
      (node (ref "K512") (pin "3") (pinfunction "3_3") (pintype "passive"))
      (node (ref "P515") (pin "1") (pinfunction "1_1") (pintype "passive"))
    )
    (net (code "88") (name "Net-(K512-Pad4)") (class "Default")
      (node (ref "K512") (pin "4") (pinfunction "4_4") (pintype "passive"))
      (node (ref "P515") (pin "3") (pinfunction "3_3") (pintype "passive"))
    )
    (net (code "89") (name "Net-(K512-Pad5)") (class "Default")
      (node (ref "K512") (pin "5") (pinfunction "5_5") (pintype "passive"))
      (node (ref "P515") (pin "2") (pinfunction "2_2") (pintype "passive"))
    )
    (net (code "90") (name "Net-(K513-Pad3)") (class "Default")
      (node (ref "K513") (pin "3") (pinfunction "3_3") (pintype "passive"))
      (node (ref "P516") (pin "1") (pinfunction "1_1") (pintype "passive"))
    )
    (net (code "91") (name "Net-(K513-Pad4)") (class "Default")
      (node (ref "K513") (pin "4") (pinfunction "4_4") (pintype "passive"))
      (node (ref "P516") (pin "2") (pinfunction "2_2") (pintype "passive"))
    )
    (net (code "92") (name "Net-(K514-Pad3)") (class "Default")
      (node (ref "K514") (pin "3") (pinfunction "3_3") (pintype "passive"))
      (node (ref "P518") (pin "1") (pinfunction "1_1") (pintype "passive"))
    )
    (net (code "93") (name "Net-(K514-Pad4)") (class "Default")
      (node (ref "K514") (pin "4") (pinfunction "4_4") (pintype "passive"))
      (node (ref "P518") (pin "2") (pinfunction "2_2") (pintype "passive"))
    )
    (net (code "94") (name "Net-(K515-Pad3)") (class "Default")
      (node (ref "K515") (pin "3") (pinfunction "3_3") (pintype "passive"))
      (node (ref "P519") (pin "1") (pinfunction "1_1") (pintype "passive"))
    )
    (net (code "95") (name "Net-(K515-Pad4)") (class "Default")
      (node (ref "K515") (pin "4") (pinfunction "4_4") (pintype "passive"))
      (node (ref "P519") (pin "2") (pinfunction "2_2") (pintype "passive"))
    )
    (net (code "96") (name "Net-(Q500-B)") (class "Default")
      (node (ref "Q500") (pin "1") (pinfunction "B_1") (pintype "passive"))
      (node (ref "R504") (pin "2") (pinfunction "2_2") (pintype "passive"))
    )
    (net (code "97") (name "Net-(Q500-C)") (class "Default")
      (node (ref "K500") (pin "2") (pinfunction "2_2") (pintype "passive"))
      (node (ref "Q500") (pin "3") (pinfunction "C_3") (pintype "passive"))
      (node (ref "Q501") (pin "2") (pinfunction "C_2") (pintype "passive"))
      (node (ref "Q501") (pin "4") (pinfunction "C_4") (pintype "passive"))
      (node (ref "R500") (pin "2") (pinfunction "2_2") (pintype "passive"))
    )
    (net (code "98") (name "Net-(Q500-E)") (class "Default")
      (node (ref "Q500") (pin "2") (pinfunction "E_2") (pintype "passive"))
      (node (ref "Q501") (pin "1") (pinfunction "B_1") (pintype "passive"))
    )
    (net (code "99") (name "Net-(Q502-B)") (class "Default")
      (node (ref "Q502") (pin "1") (pinfunction "B_1") (pintype "passive"))
      (node (ref "R509") (pin "2") (pinfunction "2_2") (pintype "passive"))
    )
    (net (code "100") (name "Net-(Q502-C)") (class "Default")
      (node (ref "K508") (pin "2") (pinfunction "2_2") (pintype "passive"))
      (node (ref "Q502") (pin "3") (pinfunction "C_3") (pintype "passive"))
      (node (ref "Q503") (pin "2") (pinfunction "C_2") (pintype "passive"))
      (node (ref "Q503") (pin "4") (pinfunction "C_4") (pintype "passive"))
      (node (ref "R510") (pin "2") (pinfunction "2_2") (pintype "passive"))
    )
    (net (code "101") (name "Net-(Q502-E)") (class "Default")
      (node (ref "Q502") (pin "2") (pinfunction "E_2") (pintype "passive"))
      (node (ref "Q503") (pin "1") (pinfunction "B_1") (pintype "passive"))
    )
    (net (code "102") (name "Net-(U500-Q1)") (class "Default")
      (node (ref "R504") (pin "1") (pinfunction "1_1") (pintype "passive"))
      (node (ref "U500") (pin "2") (pinfunction "Q1_2") (pintype "tri_state"))
    )
    (net (code "103") (name "Net-(U500-Q2)") (class "Default")
      (node (ref "U500") (pin "5") (pinfunction "Q2_5") (pintype "tri_state"))
      (node (ref "U501") (pin "1") (pinfunction "IN1_1") (pintype "input"))
    )
    (net (code "104") (name "Net-(U500-Q3)") (class "Default")
      (node (ref "U500") (pin "6") (pinfunction "Q3_6") (pintype "tri_state"))
      (node (ref "U501") (pin "2") (pinfunction "IN2_2") (pintype "input"))
    )
    (net (code "105") (name "Net-(U500-Q4)") (class "Default")
      (node (ref "U500") (pin "9") (pinfunction "Q4_9") (pintype "tri_state"))
      (node (ref "U501") (pin "3") (pinfunction "IN3_3") (pintype "input"))
    )
    (net (code "106") (name "Net-(U500-Q5)") (class "Default")
      (node (ref "U500") (pin "12") (pinfunction "Q5_12") (pintype "tri_state"))
      (node (ref "U501") (pin "4") (pinfunction "IN4_4") (pintype "input"))
    )
    (net (code "107") (name "Net-(U500-Q6)") (class "Default")
      (node (ref "U500") (pin "15") (pinfunction "Q6_15") (pintype "tri_state"))
      (node (ref "U501") (pin "5") (pinfunction "IN5_5") (pintype "input"))
    )
    (net (code "108") (name "Net-(U500-Q7)") (class "Default")
      (node (ref "U500") (pin "16") (pinfunction "Q7_16") (pintype "tri_state"))
      (node (ref "U501") (pin "6") (pinfunction "IN6_6") (pintype "input"))
    )
    (net (code "109") (name "Net-(U500-Q8)") (class "Default")
      (node (ref "U500") (pin "19") (pinfunction "Q8_19") (pintype "tri_state"))
      (node (ref "U501") (pin "7") (pinfunction "IN7_7") (pintype "input"))
    )
    (net (code "110") (name "Net-(U501-OUT1)") (class "Default")
      (node (ref "K501") (pin "2") (pinfunction "2_2") (pintype "passive"))
      (node (ref "R501") (pin "2") (pinfunction "2_2") (pintype "passive"))
      (node (ref "U501") (pin "16") (pinfunction "OUT1_16") (pintype "open_collector"))
    )
    (net (code "111") (name "Net-(U501-OUT2)") (class "Default")
      (node (ref "K502") (pin "2") (pinfunction "2_2") (pintype "passive"))
      (node (ref "R502") (pin "2") (pinfunction "2_2") (pintype "passive"))
      (node (ref "U501") (pin "15") (pinfunction "OUT2_15") (pintype "open_collector"))
    )
    (net (code "112") (name "Net-(U501-OUT3)") (class "Default")
      (node (ref "K503") (pin "2") (pinfunction "2_2") (pintype "passive"))
      (node (ref "R503") (pin "2") (pinfunction "2_2") (pintype "passive"))
      (node (ref "U501") (pin "14") (pinfunction "OUT3_14") (pintype "open_collector"))
    )
    (net (code "113") (name "Net-(U501-OUT4)") (class "Default")
      (node (ref "K504") (pin "2") (pinfunction "2_2") (pintype "passive"))
      (node (ref "R505") (pin "2") (pinfunction "2_2") (pintype "passive"))
      (node (ref "U501") (pin "13") (pinfunction "OUT4_13") (pintype "open_collector"))
    )
    (net (code "114") (name "Net-(U501-OUT5)") (class "Default")
      (node (ref "K505") (pin "2") (pinfunction "2_2") (pintype "passive"))
      (node (ref "R506") (pin "2") (pinfunction "2_2") (pintype "passive"))
      (node (ref "U501") (pin "12") (pinfunction "OUT5_12") (pintype "open_collector"))
    )
    (net (code "115") (name "Net-(U501-OUT6)") (class "Default")
      (node (ref "K506") (pin "2") (pinfunction "2_2") (pintype "passive"))
      (node (ref "R507") (pin "2") (pinfunction "2_2") (pintype "passive"))
      (node (ref "U501") (pin "11") (pinfunction "OUT6_11") (pintype "open_collector"))
    )
    (net (code "116") (name "Net-(U501-OUT7)") (class "Default")
      (node (ref "K507") (pin "2") (pinfunction "2_2") (pintype "passive"))
      (node (ref "R508") (pin "2") (pinfunction "2_2") (pintype "passive"))
      (node (ref "U501") (pin "10") (pinfunction "OUT7_10") (pintype "open_collector"))
    )
    (net (code "117") (name "Net-(U502-Q1)") (class "Default")
      (node (ref "R509") (pin "1") (pinfunction "1_1") (pintype "passive"))
      (node (ref "U502") (pin "2") (pinfunction "Q1_2") (pintype "tri_state"))
    )
    (net (code "118") (name "Net-(U502-Q2)") (class "Default")
      (node (ref "U502") (pin "5") (pinfunction "Q2_5") (pintype "tri_state"))
      (node (ref "U503") (pin "1") (pinfunction "IN1_1") (pintype "input"))
    )
    (net (code "119") (name "Net-(U502-Q3)") (class "Default")
      (node (ref "U502") (pin "6") (pinfunction "Q3_6") (pintype "tri_state"))
      (node (ref "U503") (pin "2") (pinfunction "IN2_2") (pintype "input"))
    )
    (net (code "120") (name "Net-(U502-Q4)") (class "Default")
      (node (ref "U502") (pin "9") (pinfunction "Q4_9") (pintype "tri_state"))
      (node (ref "U503") (pin "3") (pinfunction "IN3_3") (pintype "input"))
    )
    (net (code "121") (name "Net-(U502-Q5)") (class "Default")
      (node (ref "U502") (pin "12") (pinfunction "Q5_12") (pintype "tri_state"))
      (node (ref "U503") (pin "4") (pinfunction "IN4_4") (pintype "input"))
    )
    (net (code "122") (name "Net-(U502-Q6)") (class "Default")
      (node (ref "U502") (pin "15") (pinfunction "Q6_15") (pintype "tri_state"))
      (node (ref "U503") (pin "5") (pinfunction "IN5_5") (pintype "input"))
    )
    (net (code "123") (name "Net-(U502-Q7)") (class "Default")
      (node (ref "U502") (pin "16") (pinfunction "Q7_16") (pintype "tri_state"))
      (node (ref "U503") (pin "6") (pinfunction "IN6_6") (pintype "input"))
    )
    (net (code "124") (name "Net-(U502-Q8)") (class "Default")
      (node (ref "U502") (pin "19") (pinfunction "Q8_19") (pintype "tri_state"))
      (node (ref "U503") (pin "7") (pinfunction "IN7_7") (pintype "input"))
    )
    (net (code "125") (name "Net-(U503-OUT1)") (class "Default")
      (node (ref "K509") (pin "2") (pinfunction "2_2") (pintype "passive"))
      (node (ref "R511") (pin "2") (pinfunction "2_2") (pintype "passive"))
      (node (ref "U503") (pin "16") (pinfunction "OUT1_16") (pintype "open_collector"))
    )
    (net (code "126") (name "Net-(U503-OUT2)") (class "Default")
      (node (ref "K510") (pin "2") (pinfunction "2_2") (pintype "passive"))
      (node (ref "R512") (pin "2") (pinfunction "2_2") (pintype "passive"))
      (node (ref "U503") (pin "15") (pinfunction "OUT2_15") (pintype "open_collector"))
    )
    (net (code "127") (name "Net-(U503-OUT3)") (class "Default")
      (node (ref "K511") (pin "2") (pinfunction "2_2") (pintype "passive"))
      (node (ref "R513") (pin "2") (pinfunction "2_2") (pintype "passive"))
      (node (ref "U503") (pin "14") (pinfunction "OUT3_14") (pintype "open_collector"))
    )
    (net (code "128") (name "Net-(U503-OUT4)") (class "Default")
      (node (ref "K512") (pin "2") (pinfunction "2_2") (pintype "passive"))
      (node (ref "R514") (pin "2") (pinfunction "2_2") (pintype "passive"))
      (node (ref "U503") (pin "13") (pinfunction "OUT4_13") (pintype "open_collector"))
    )
    (net (code "129") (name "Net-(U503-OUT5)") (class "Default")
      (node (ref "K513") (pin "2") (pinfunction "2_2") (pintype "passive"))
      (node (ref "R515") (pin "2") (pinfunction "2_2") (pintype "passive"))
      (node (ref "U503") (pin "12") (pinfunction "OUT5_12") (pintype "open_collector"))
    )
    (net (code "130") (name "Net-(U503-OUT6)") (class "Default")
      (node (ref "K514") (pin "2") (pinfunction "2_2") (pintype "passive"))
      (node (ref "R516") (pin "2") (pinfunction "2_2") (pintype "passive"))
      (node (ref "U503") (pin "11") (pinfunction "OUT6_11") (pintype "open_collector"))
    )
    (net (code "131") (name "Net-(U503-OUT7)") (class "Default")
      (node (ref "K515") (pin "2") (pinfunction "2_2") (pintype "passive"))
      (node (ref "R517") (pin "2") (pinfunction "2_2") (pintype "passive"))
      (node (ref "U503") (pin "10") (pinfunction "OUT7_10") (pintype "open_collector"))
    )
    (net (code "132") (name "VSS") (class "Default")
      (node (ref "P500") (pin "11") (pinfunction "11_11") (pintype "passive"))
      (node (ref "P500") (pin "14") (pinfunction "14_14") (pintype "passive"))
      (node (ref "P514") (pin "11") (pinfunction "11_11") (pintype "passive"))
      (node (ref "P514") (pin "14") (pinfunction "14_14") (pintype "passive"))
    )
    (net (code "133") (name "VSS_O1") (class "Default")
      (node (ref "C501") (pin "2") (pinfunction "2_2") (pintype "passive"))
      (node (ref "P517") (pin "14") (pinfunction "14_14") (pintype "passive"))
      (node (ref "P517") (pin "8") (pinfunction "8_8") (pintype "passive"))
      (node (ref "Q503") (pin "3") (pinfunction "E_3") (pintype "passive"))
      (node (ref "U502") (pin "10") (pinfunction "GND_10") (pintype "power_in"))
      (node (ref "U503") (pin "8") (pinfunction "GND_8") (pintype "power_in"))
    )
    (net (code "134") (name "VSS_O2") (class "Default")
      (node (ref "C500") (pin "2") (pinfunction "2_2") (pintype "passive"))
      (node (ref "P503") (pin "14") (pinfunction "14_14") (pintype "passive"))
      (node (ref "P503") (pin "8") (pinfunction "8_8") (pintype "passive"))
      (node (ref "Q501") (pin "3") (pinfunction "E_3") (pintype "passive"))
      (node (ref "U500") (pin "10") (pinfunction "GND_10") (pintype "power_in"))
      (node (ref "U501") (pin "8") (pinfunction "GND_8") (pintype "power_in"))
    )
    (net (code "135") (name "unconnected-(K508-Pad5)") (class "Default")
      (node (ref "K508") (pin "5") (pinfunction "5_5") (pintype "passive"))
    )
    (net (code "136") (name "unconnected-(K509-Pad5)") (class "Default")
      (node (ref "K509") (pin "5") (pinfunction "5_5") (pintype "passive"))
    )
    (net (code "137") (name "unconnected-(K510-Pad5)") (class "Default")
      (node (ref "K510") (pin "5") (pinfunction "5_5") (pintype "passive"))
    )
    (net (code "138") (name "unconnected-(K513-Pad5)") (class "Default")
      (node (ref "K513") (pin "5") (pinfunction "5_5") (pintype "passive"))
    )
    (net (code "139") (name "unconnected-(K514-Pad5)") (class "Default")
      (node (ref "K514") (pin "5") (pinfunction "5_5") (pintype "passive"))
    )
    (net (code "140") (name "unconnected-(K515-Pad5)") (class "Default")
      (node (ref "K515") (pin "5") (pinfunction "5_5") (pintype "passive"))
    )
  )
)
